# SH4_-_CAN.net
KiCad netlist of a schematic drawn in Altium Designer
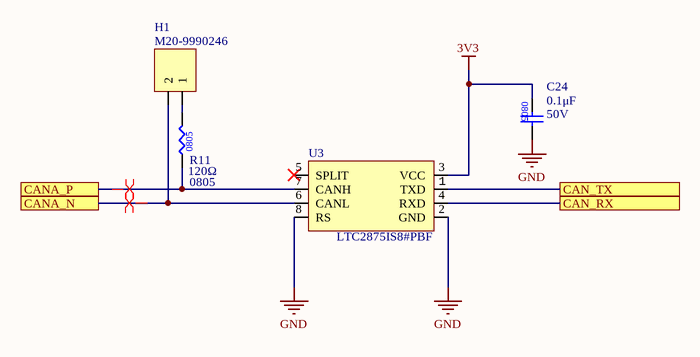
[diagram p0: SH4 - CAN.SchDoc]

(export (version "E")
  (design (tool "Eeschema 10.0.6"))
  (components
    (comp (ref "C24")
      (value "0.1μF")
      (footprint "CAP2012")
      (description "CAP CER 0.1UF 50V X7R 0805")
      (fields
        (field (name "VOLTAGE RATING") "50V")
        (field (name "LCSC PART #") "C49678")
        (field (name "Comment") "CAP_0.1uF_50V_0805")
      )
      (libsource (lib "UWRT_Schematic_Library_2020") (part "CAP_0.1uF_50V_0805"))
    )
    (comp (ref "H1")
      (value "JUMPER")
      (footprint "HDR1X2")
      (description "HEADER 2X1")
      (fields (field (name "MANUFACTURER PART NUMBER 1") "M20-9990246"))
      (libsource (lib "UWRT_Schematic_Library_2020") (part "JUMPER"))
    )
    (comp (ref "R11")
      (value "120Ω")
      (footprint "RES0805")
      (description "RES 120 OHM 1% 1/8W 0805")
      (fields
        (field (name "LCSC PART #") "C17437")
        (field (name "PACKAGE/FOOTPRINT") "0805")
        (field (name "Comment") "RES_120Ω_0805_1%")
      )
      (libsource (lib "UWRT_Schematic_Library_2020") (part "RES_120Ω_0805_1%"))
    )
    (comp (ref "U3")
      (value "IC_CAN_TRANSCEIVER")
      (footprint "LT-S8_N")
      (description "IC TXRX CAN 4MBPS 8SO")
      (fields
        (field (name "MANUFACTURER PART NUMBER 1") "LTC2875IS8#PBF")
        (field (name "LCSC PART #") "C117076")
      )
      (libsource (lib "UWRT_Schematic_Library_2020") (part "IC_CAN_TRANSCEIVER"))
    )
  )
  (nets
    (net (code "1") (name "/CANA_N") (class "Default")
      (node (ref "H1") (pin "2") (pinfunction "2_2") (pintype "passive"))
      (node (ref "U3") (pin "6") (pinfunction "CANL_6") (pintype "passive"))
    )
    (net (code "2") (name "/CANA_P") (class "Default")
      (node (ref "R11") (pin "1") (pinfunction "1_1") (pintype "passive"))
      (node (ref "U3") (pin "7") (pinfunction "CANH_7") (pintype "passive"))
    )
    (net (code "3") (name "/CAN_RX") (class "Default")
      (node (ref "U3") (pin "4") (pinfunction "RXD_4") (pintype "passive"))
    )
    (net (code "4") (name "/CAN_TX") (class "Default")
      (node (ref "U3") (pin "1") (pinfunction "TXD_1") (pintype "passive"))
    )
    (net (code "5") (name "3V3") (class "Default")
      (node (ref "C24") (pin "1") (pinfunction "1_1") (pintype "passive"))
      (node (ref "U3") (pin "3") (pinfunction "VCC_3") (pintype "passive"))
    )
    (net (code "6") (name "GND") (class "Default")
      (node (ref "C24") (pin "2") (pinfunction "2_2") (pintype "passive"))
      (node (ref "U3") (pin "2") (pinfunction "GND_2") (pintype "passive"))
      (node (ref "U3") (pin "8") (pinfunction "RS_8") (pintype "passive"))
    )
    (net (code "7") (name "Net-(H1-Pad1)") (class "Default")
      (node (ref "H1") (pin "1") (pinfunction "1_1") (pintype "passive"))
      (node (ref "R11") (pin "2") (pinfunction "2_2") (pintype "passive"))
    )
    (net (code "8") (name "unconnected-(U3-SPLIT-Pad5)") (class "Default")
      (node (ref "U3") (pin "5") (pinfunction "SPLIT_5") (pintype "passive+no_connect"))
    )
  )
)
